# Escubo_de_LED.net
KiCad netlist of a schematic drawn in EAGLE
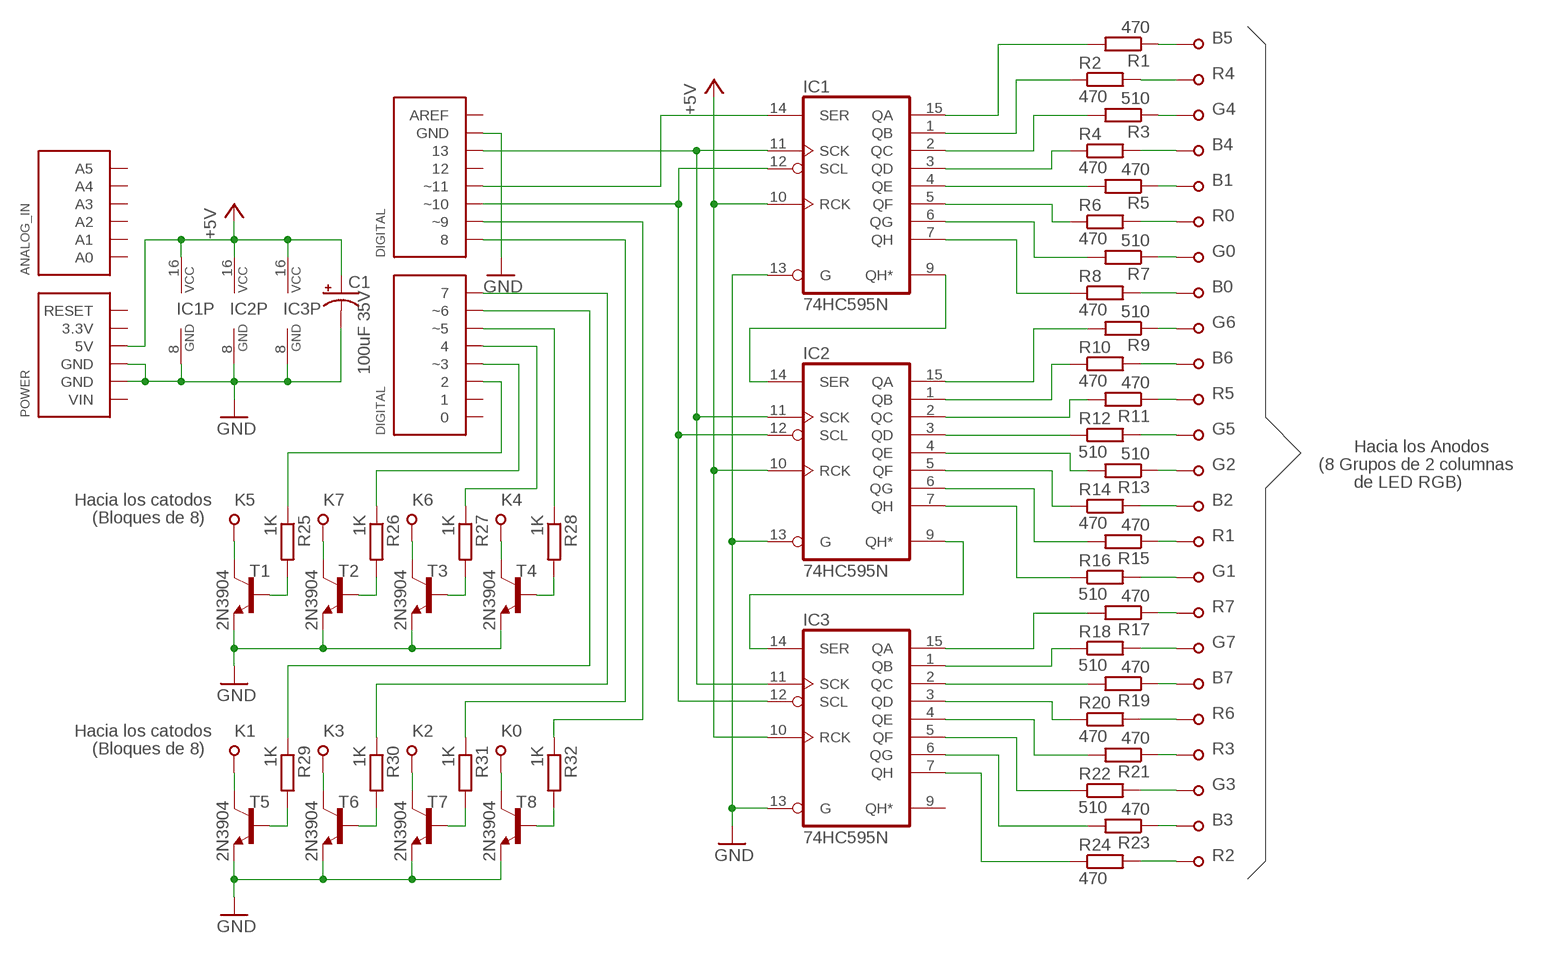
[diagram p0: schematic, sheet 1]

(export (version "E")
  (design (tool "Eeschema 10.0.6"))
  (components
    (comp (ref "C1")
      (value "100uF 35V")
      (footprint "eagle-import:E3,5-8")
      (libsource (lib "eagle-import") (part "CPOL-USE3.5-8"))
    )
    (comp (ref "IC1")
      (value "74HC595N")
      (footprint "eagle-import:DIP16")
      (libsource (lib "eagle-import") (part "74595NHC"))
    )
    (comp (ref "IC2")
      (value "74HC595N")
      (footprint "eagle-import:DIP16")
      (libsource (lib "eagle-import") (part "74595NHC"))
    )
    (comp (ref "IC3")
      (value "74HC595N")
      (footprint "eagle-import:DIP16")
      (libsource (lib "eagle-import") (part "74595NHC"))
    )
    (comp (ref "R1")
      (value "470")
      (footprint "eagle-import:0204_7")
      (libsource (lib "eagle-import") (part "R-EU_0204/7"))
    )
    (comp (ref "R2")
      (value "470")
      (footprint "eagle-import:0204_7")
      (libsource (lib "eagle-import") (part "R-EU_0204/7"))
    )
    (comp (ref "R3")
      (value "510")
      (footprint "eagle-import:0204_7")
      (libsource (lib "eagle-import") (part "R-EU_0204/7"))
    )
    (comp (ref "R4")
      (value "470")
      (footprint "eagle-import:0204_7")
      (libsource (lib "eagle-import") (part "R-EU_0204/7"))
    )
    (comp (ref "R5")
      (value "470")
      (footprint "eagle-import:0207_12")
      (libsource (lib "eagle-import") (part "R-EU_0207/12"))
    )
    (comp (ref "R6")
      (value "470")
      (footprint "eagle-import:0207_10")
      (libsource (lib "eagle-import") (part "R-EU_0207/10"))
    )
    (comp (ref "R7")
      (value "510")
      (footprint "eagle-import:0204_7")
      (libsource (lib "eagle-import") (part "R-EU_0204/7"))
    )
    (comp (ref "R8")
      (value "470")
      (footprint "eagle-import:0204_5")
      (libsource (lib "eagle-import") (part "R-EU_0204/5"))
    )
    (comp (ref "R9")
      (value "510")
      (footprint "eagle-import:0204_7")
      (libsource (lib "eagle-import") (part "R-EU_0204/7"))
    )
    (comp (ref "R10")
      (value "470")
      (footprint "eagle-import:0204_7")
      (libsource (lib "eagle-import") (part "R-EU_0204/7"))
    )
    (comp (ref "R11")
      (value "470")
      (footprint "eagle-import:0204_7")
      (libsource (lib "eagle-import") (part "R-EU_0204/7"))
    )
    (comp (ref "R12")
      (value "510")
      (footprint "eagle-import:0204_7")
      (libsource (lib "eagle-import") (part "R-EU_0204/7"))
    )
    (comp (ref "R13")
      (value "510")
      (footprint "eagle-import:0207_12")
      (libsource (lib "eagle-import") (part "R-EU_0207/12"))
    )
    (comp (ref "R14")
      (value "470")
      (footprint "eagle-import:0207_10")
      (libsource (lib "eagle-import") (part "R-EU_0207/10"))
    )
    (comp (ref "R15")
      (value "470")
      (footprint "eagle-import:0204_7")
      (libsource (lib "eagle-import") (part "R-EU_0204/7"))
    )
    (comp (ref "R16")
      (value "510")
      (footprint "eagle-import:0204_5")
      (libsource (lib "eagle-import") (part "R-EU_0204/5"))
    )
    (comp (ref "R17")
      (value "470")
      (footprint "eagle-import:0204_7")
      (libsource (lib "eagle-import") (part "R-EU_0204/7"))
    )
    (comp (ref "R18")
      (value "510")
      (footprint "eagle-import:0204_7")
      (libsource (lib "eagle-import") (part "R-EU_0204/7"))
    )
    (comp (ref "R19")
      (value "470")
      (footprint "eagle-import:0204_7")
      (libsource (lib "eagle-import") (part "R-EU_0204/7"))
    )
    (comp (ref "R20")
      (value "470")
      (footprint "eagle-import:0204_7")
      (libsource (lib "eagle-import") (part "R-EU_0204/7"))
    )
    (comp (ref "R21")
      (value "470")
      (footprint "eagle-import:0207_12")
      (libsource (lib "eagle-import") (part "R-EU_0207/12"))
    )
    (comp (ref "R22")
      (value "510")
      (footprint "eagle-import:0207_10")
      (libsource (lib "eagle-import") (part "R-EU_0207/10"))
    )
    (comp (ref "R23")
      (value "470")
      (footprint "eagle-import:0204_7")
      (libsource (lib "eagle-import") (part "R-EU_0204/7"))
    )
    (comp (ref "R24")
      (value "470")
      (footprint "eagle-import:0204_5")
      (libsource (lib "eagle-import") (part "R-EU_0204/5"))
    )
    (comp (ref "R25")
      (value "1K")
      (footprint "eagle-import:0204V")
      (libsource (lib "eagle-import") (part "R-EU_0204/2V"))
    )
    (comp (ref "R26")
      (value "1K")
      (footprint "eagle-import:0204V")
      (libsource (lib "eagle-import") (part "R-EU_0204/2V"))
    )
    (comp (ref "R27")
      (value "1K")
      (footprint "eagle-import:0204V")
      (libsource (lib "eagle-import") (part "R-EU_0204/2V"))
    )
    (comp (ref "R28")
      (value "1K")
      (footprint "eagle-import:0204V")
      (libsource (lib "eagle-import") (part "R-EU_0204/2V"))
    )
    (comp (ref "R29")
      (value "1K")
      (footprint "eagle-import:0204V")
      (libsource (lib "eagle-import") (part "R-EU_0204/2V"))
    )
    (comp (ref "R30")
      (value "1K")
      (footprint "eagle-import:0204V")
      (libsource (lib "eagle-import") (part "R-EU_0204/2V"))
    )
    (comp (ref "R31")
      (value "1K")
      (footprint "eagle-import:0204V")
      (libsource (lib "eagle-import") (part "R-EU_0204/2V"))
    )
    (comp (ref "R32")
      (value "1K")
      (footprint "eagle-import:0204V")
      (libsource (lib "eagle-import") (part "R-EU_0204/2V"))
    )
    (comp (ref "S1")
      (value "ARDUINO_SHIELD")
      (footprint "eagle-import:ARDUINO_SHIELD")
      (libsource (lib "eagle-import") (part "ARDUINO_SHIELD"))
    )
    (comp (ref "T1")
      (value "2N3904")
      (footprint "eagle-import:TO92-EBC")
      (libsource (lib "eagle-import") (part "-NPN-TO92-EBC2N3904"))
    )
    (comp (ref "T2")
      (value "2N3904")
      (footprint "eagle-import:TO92-EBC")
      (libsource (lib "eagle-import") (part "-NPN-TO92-EBC2N3904"))
    )
    (comp (ref "T3")
      (value "2N3904")
      (footprint "eagle-import:TO92-EBC")
      (libsource (lib "eagle-import") (part "-NPN-TO92-EBC2N3904"))
    )
    (comp (ref "T4")
      (value "2N3904")
      (footprint "eagle-import:TO92-EBC")
      (libsource (lib "eagle-import") (part "-NPN-TO92-EBC2N3904"))
    )
    (comp (ref "T5")
      (value "2N3904")
      (footprint "eagle-import:TO92-EBC")
      (libsource (lib "eagle-import") (part "-NPN-TO92-EBC2N3904"))
    )
    (comp (ref "T6")
      (value "2N3904")
      (footprint "eagle-import:TO92-EBC")
      (libsource (lib "eagle-import") (part "-NPN-TO92-EBC2N3904"))
    )
    (comp (ref "T7")
      (value "2N3904")
      (footprint "eagle-import:TO92-EBC")
      (libsource (lib "eagle-import") (part "-NPN-TO92-EBC2N3904"))
    )
    (comp (ref "T8")
      (value "2N3904")
      (footprint "eagle-import:TO92-EBC")
      (libsource (lib "eagle-import") (part "-NPN-TO92-EBC2N3904"))
    )
    (comp (ref "U$1")
      (value "PAD_SIMPLE_PTH")
      (footprint "eagle-import:PAD_SIMPLE_PTH")
      (libsource (lib "eagle-import") (part "PAD_SIMPLE_PTH"))
    )
    (comp (ref "U$2")
      (value "PAD_SIMPLE_PTH")
      (footprint "eagle-import:PAD_SIMPLE_PTH")
      (libsource (lib "eagle-import") (part "PAD_SIMPLE_PTH"))
    )
    (comp (ref "U$3")
      (value "PAD_SIMPLE_PTH")
      (footprint "eagle-import:PAD_SIMPLE_PTH")
      (libsource (lib "eagle-import") (part "PAD_SIMPLE_PTH"))
    )
    (comp (ref "U$4")
      (value "PAD_SIMPLE_PTH")
      (footprint "eagle-import:PAD_SIMPLE_PTH")
      (libsource (lib "eagle-import") (part "PAD_SIMPLE_PTH"))
    )
    (comp (ref "U$5")
      (value "PAD_SIMPLE_PTH")
      (footprint "eagle-import:PAD_SIMPLE_PTH")
      (libsource (lib "eagle-import") (part "PAD_SIMPLE_PTH"))
    )
    (comp (ref "U$6")
      (value "PAD_SIMPLE_PTH")
      (footprint "eagle-import:PAD_SIMPLE_PTH")
      (libsource (lib "eagle-import") (part "PAD_SIMPLE_PTH"))
    )
    (comp (ref "U$7")
      (value "PAD_SIMPLE_PTH")
      (footprint "eagle-import:PAD_SIMPLE_PTH")
      (libsource (lib "eagle-import") (part "PAD_SIMPLE_PTH"))
    )
    (comp (ref "U$8")
      (value "PAD_SIMPLE_PTH")
      (footprint "eagle-import:PAD_SIMPLE_PTH")
      (libsource (lib "eagle-import") (part "PAD_SIMPLE_PTH"))
    )
    (comp (ref "U$9")
      (value "PAD_SIMPLE_PTH")
      (footprint "eagle-import:PAD_SIMPLE_PTH")
      (libsource (lib "eagle-import") (part "PAD_SIMPLE_PTH"))
    )
    (comp (ref "U$10")
      (value "PAD_SIMPLE_PTH")
      (footprint "eagle-import:PAD_SIMPLE_PTH")
      (libsource (lib "eagle-import") (part "PAD_SIMPLE_PTH"))
    )
    (comp (ref "U$11")
      (value "PAD_SIMPLE_PTH")
      (footprint "eagle-import:PAD_SIMPLE_PTH")
      (libsource (lib "eagle-import") (part "PAD_SIMPLE_PTH"))
    )
    (comp (ref "U$12")
      (value "PAD_SIMPLE_PTH")
      (footprint "eagle-import:PAD_SIMPLE_PTH")
      (libsource (lib "eagle-import") (part "PAD_SIMPLE_PTH"))
    )
    (comp (ref "U$13")
      (value "PAD_SIMPLE_PTH")
      (footprint "eagle-import:PAD_SIMPLE_PTH")
      (libsource (lib "eagle-import") (part "PAD_SIMPLE_PTH"))
    )
    (comp (ref "U$14")
      (value "PAD_SIMPLE_PTH")
      (footprint "eagle-import:PAD_SIMPLE_PTH")
      (libsource (lib "eagle-import") (part "PAD_SIMPLE_PTH"))
    )
    (comp (ref "U$15")
      (value "PAD_SIMPLE_PTH")
      (footprint "eagle-import:PAD_SIMPLE_PTH")
      (libsource (lib "eagle-import") (part "PAD_SIMPLE_PTH"))
    )
    (comp (ref "U$16")
      (value "PAD_SIMPLE_PTH")
      (footprint "eagle-import:PAD_SIMPLE_PTH")
      (libsource (lib "eagle-import") (part "PAD_SIMPLE_PTH"))
    )
    (comp (ref "U$17")
      (value "PAD_SIMPLE_PTH")
      (footprint "eagle-import:PAD_SIMPLE_PTH")
      (libsource (lib "eagle-import") (part "PAD_SIMPLE_PTH"))
    )
    (comp (ref "U$18")
      (value "PAD_SIMPLE_PTH")
      (footprint "eagle-import:PAD_SIMPLE_PTH")
      (libsource (lib "eagle-import") (part "PAD_SIMPLE_PTH"))
    )
    (comp (ref "U$19")
      (value "PAD_SIMPLE_PTH")
      (footprint "eagle-import:PAD_SIMPLE_PTH")
      (libsource (lib "eagle-import") (part "PAD_SIMPLE_PTH"))
    )
    (comp (ref "U$20")
      (value "PAD_SIMPLE_PTH")
      (footprint "eagle-import:PAD_SIMPLE_PTH")
      (libsource (lib "eagle-import") (part "PAD_SIMPLE_PTH"))
    )
    (comp (ref "U$21")
      (value "PAD_SIMPLE_PTH")
      (footprint "eagle-import:PAD_SIMPLE_PTH")
      (libsource (lib "eagle-import") (part "PAD_SIMPLE_PTH"))
    )
    (comp (ref "U$22")
      (value "PAD_SIMPLE_PTH")
      (footprint "eagle-import:PAD_SIMPLE_PTH")
      (libsource (lib "eagle-import") (part "PAD_SIMPLE_PTH"))
    )
    (comp (ref "U$23")
      (value "PAD_SIMPLE_PTH")
      (footprint "eagle-import:PAD_SIMPLE_PTH")
      (libsource (lib "eagle-import") (part "PAD_SIMPLE_PTH"))
    )
    (comp (ref "U$24")
      (value "PAD_SIMPLE_PTH")
      (footprint "eagle-import:PAD_SIMPLE_PTH")
      (libsource (lib "eagle-import") (part "PAD_SIMPLE_PTH"))
    )
    (comp (ref "U$25")
      (value "PAD_SIMPLE_PTH")
      (footprint "eagle-import:PAD_SIMPLE_PTH")
      (libsource (lib "eagle-import") (part "PAD_SIMPLE_PTH"))
    )
    (comp (ref "U$26")
      (value "PAD_SIMPLE_PTH")
      (footprint "eagle-import:PAD_SIMPLE_PTH")
      (libsource (lib "eagle-import") (part "PAD_SIMPLE_PTH"))
    )
    (comp (ref "U$27")
      (value "PAD_SIMPLE_PTH")
      (footprint "eagle-import:PAD_SIMPLE_PTH")
      (libsource (lib "eagle-import") (part "PAD_SIMPLE_PTH"))
    )
    (comp (ref "U$28")
      (value "PAD_SIMPLE_PTH")
      (footprint "eagle-import:PAD_SIMPLE_PTH")
      (libsource (lib "eagle-import") (part "PAD_SIMPLE_PTH"))
    )
    (comp (ref "U$29")
      (value "PAD_SIMPLE_PTH")
      (footprint "eagle-import:PAD_SIMPLE_PTH")
      (libsource (lib "eagle-import") (part "PAD_SIMPLE_PTH"))
    )
    (comp (ref "U$30")
      (value "PAD_SIMPLE_PTH")
      (footprint "eagle-import:PAD_SIMPLE_PTH")
      (libsource (lib "eagle-import") (part "PAD_SIMPLE_PTH"))
    )
    (comp (ref "U$31")
      (value "PAD_SIMPLE_PTH")
      (footprint "eagle-import:PAD_SIMPLE_PTH")
      (libsource (lib "eagle-import") (part "PAD_SIMPLE_PTH"))
    )
    (comp (ref "U$32")
      (value "PAD_SIMPLE_PTH")
      (footprint "eagle-import:PAD_SIMPLE_PTH")
      (libsource (lib "eagle-import") (part "PAD_SIMPLE_PTH"))
    )
  )
  (nets
    (net (code "1") (name "+5V") (class "Default")
      (node (ref "C1") (pin "+") (pinfunction "+_+") (pintype "passive"))
      (node (ref "IC1") (pin "10") (pinfunction "RCK_10") (pintype "input"))
      (node (ref "IC1") (pin "16") (pinfunction "VCC_16") (pintype "power_in"))
      (node (ref "IC2") (pin "10") (pinfunction "RCK_10") (pintype "input"))
      (node (ref "IC2") (pin "16") (pinfunction "VCC_16") (pintype "power_in"))
      (node (ref "IC3") (pin "10") (pinfunction "RCK_10") (pintype "input"))
      (node (ref "IC3") (pin "16") (pinfunction "VCC_16") (pintype "power_in"))
      (node (ref "S1") (pin "5V") (pinfunction "5V_5V") (pintype "bidirectional"))
    )
    (net (code "2") (name "GND") (class "Default")
      (node (ref "C1") (pin "-") (pinfunction "-_-") (pintype "passive"))
      (node (ref "IC1") (pin "13") (pinfunction "G_13") (pintype "input"))
      (node (ref "IC1") (pin "8") (pinfunction "GND_8") (pintype "power_in"))
      (node (ref "IC2") (pin "13") (pinfunction "G_13") (pintype "input"))
      (node (ref "IC2") (pin "8") (pinfunction "GND_8") (pintype "power_in"))
      (node (ref "IC3") (pin "13") (pinfunction "G_13") (pintype "input"))
      (node (ref "IC3") (pin "8") (pinfunction "GND_8") (pintype "power_in"))
      (node (ref "S1") (pin "GND") (pinfunction "GND_GND") (pintype "bidirectional"))
      (node (ref "S1") (pin "GND@1") (pinfunction "GND_GND@1") (pintype "bidirectional"))
      (node (ref "S1") (pin "GND@2") (pinfunction "GND_GND@2") (pintype "bidirectional"))
      (node (ref "T1") (pin "E") (pinfunction "E_E") (pintype "passive"))
      (node (ref "T2") (pin "E") (pinfunction "E_E") (pintype "passive"))
      (node (ref "T3") (pin "E") (pinfunction "E_E") (pintype "passive"))
      (node (ref "T4") (pin "E") (pinfunction "E_E") (pintype "passive"))
      (node (ref "T5") (pin "E") (pinfunction "E_E") (pintype "passive"))
      (node (ref "T6") (pin "E") (pinfunction "E_E") (pintype "passive"))
      (node (ref "T7") (pin "E") (pinfunction "E_E") (pintype "passive"))
      (node (ref "T8") (pin "E") (pinfunction "E_E") (pintype "passive"))
    )
    (net (code "3") (name "Net-(IC1A-QA)") (class "Default")
      (node (ref "IC1") (pin "15") (pinfunction "QA_15") (pintype "tri_state"))
      (node (ref "R1") (pin "2") (pinfunction "2_2") (pintype "passive"))
    )
    (net (code "4") (name "Net-(IC1A-QB)") (class "Default")
      (node (ref "IC1") (pin "1") (pinfunction "QB_1") (pintype "tri_state"))
      (node (ref "R2") (pin "1") (pinfunction "1_1") (pintype "passive"))
    )
    (net (code "5") (name "Net-(IC1A-QC)") (class "Default")
      (node (ref "IC1") (pin "2") (pinfunction "QC_2") (pintype "tri_state"))
      (node (ref "R3") (pin "2") (pinfunction "2_2") (pintype "passive"))
    )
    (net (code "6") (name "Net-(IC1A-QD)") (class "Default")
      (node (ref "IC1") (pin "3") (pinfunction "QD_3") (pintype "tri_state"))
      (node (ref "R4") (pin "1") (pinfunction "1_1") (pintype "passive"))
    )
    (net (code "7") (name "Net-(IC1A-QE)") (class "Default")
      (node (ref "IC1") (pin "4") (pinfunction "QE_4") (pintype "tri_state"))
      (node (ref "R5") (pin "2") (pinfunction "2_2") (pintype "passive"))
    )
    (net (code "8") (name "Net-(IC1A-QF)") (class "Default")
      (node (ref "IC1") (pin "5") (pinfunction "QF_5") (pintype "tri_state"))
      (node (ref "R6") (pin "1") (pinfunction "1_1") (pintype "passive"))
    )
    (net (code "9") (name "Net-(IC1A-QG)") (class "Default")
      (node (ref "IC1") (pin "6") (pinfunction "QG_6") (pintype "tri_state"))
      (node (ref "R7") (pin "2") (pinfunction "2_2") (pintype "passive"))
    )
    (net (code "10") (name "Net-(IC1A-QH)") (class "Default")
      (node (ref "IC1") (pin "7") (pinfunction "QH_7") (pintype "tri_state"))
      (node (ref "R8") (pin "1") (pinfunction "1_1") (pintype "passive"))
    )
    (net (code "11") (name "Net-(IC1A-QH*)") (class "Default")
      (node (ref "IC1") (pin "9") (pinfunction "QH*_9") (pintype "tri_state"))
      (node (ref "IC2") (pin "14") (pinfunction "SER_14") (pintype "input"))
    )
    (net (code "12") (name "Net-(IC1A-SCK)") (class "Default")
      (node (ref "IC1") (pin "11") (pinfunction "SCK_11") (pintype "input"))
      (node (ref "IC2") (pin "11") (pinfunction "SCK_11") (pintype "input"))
      (node (ref "IC3") (pin "11") (pinfunction "SCK_11") (pintype "input"))
      (node (ref "S1") (pin "13") (pinfunction "13_13") (pintype "bidirectional"))
    )
    (net (code "13") (name "Net-(IC1A-SCL)") (class "Default")
      (node (ref "IC1") (pin "12") (pinfunction "SCL_12") (pintype "input"))
      (node (ref "IC2") (pin "12") (pinfunction "SCL_12") (pintype "input"))
      (node (ref "IC3") (pin "12") (pinfunction "SCL_12") (pintype "input"))
      (node (ref "S1") (pin "~10") (pinfunction "~{10}_~10") (pintype "bidirectional"))
    )
    (net (code "14") (name "Net-(IC1A-SER)") (class "Default")
      (node (ref "IC1") (pin "14") (pinfunction "SER_14") (pintype "input"))
      (node (ref "S1") (pin "~11") (pinfunction "~{11}_~11") (pintype "bidirectional"))
    )
    (net (code "15") (name "Net-(IC2A-QA)") (class "Default")
      (node (ref "IC2") (pin "15") (pinfunction "QA_15") (pintype "tri_state"))
      (node (ref "R9") (pin "2") (pinfunction "2_2") (pintype "passive"))
    )
    (net (code "16") (name "Net-(IC2A-QB)") (class "Default")
      (node (ref "IC2") (pin "1") (pinfunction "QB_1") (pintype "tri_state"))
      (node (ref "R10") (pin "1") (pinfunction "1_1") (pintype "passive"))
    )
    (net (code "17") (name "Net-(IC2A-QC)") (class "Default")
      (node (ref "IC2") (pin "2") (pinfunction "QC_2") (pintype "tri_state"))
      (node (ref "R11") (pin "2") (pinfunction "2_2") (pintype "passive"))
    )
    (net (code "18") (name "Net-(IC2A-QD)") (class "Default")
      (node (ref "IC2") (pin "3") (pinfunction "QD_3") (pintype "tri_state"))
      (node (ref "R12") (pin "1") (pinfunction "1_1") (pintype "passive"))
    )
    (net (code "19") (name "Net-(IC2A-QE)") (class "Default")
      (node (ref "IC2") (pin "4") (pinfunction "QE_4") (pintype "tri_state"))
      (node (ref "R13") (pin "2") (pinfunction "2_2") (pintype "passive"))
    )
    (net (code "20") (name "Net-(IC2A-QF)") (class "Default")
      (node (ref "IC2") (pin "5") (pinfunction "QF_5") (pintype "tri_state"))
      (node (ref "R14") (pin "1") (pinfunction "1_1") (pintype "passive"))
    )
    (net (code "21") (name "Net-(IC2A-QG)") (class "Default")
      (node (ref "IC2") (pin "6") (pinfunction "QG_6") (pintype "tri_state"))
      (node (ref "R15") (pin "2") (pinfunction "2_2") (pintype "passive"))
    )
    (net (code "22") (name "Net-(IC2A-QH)") (class "Default")
      (node (ref "IC2") (pin "7") (pinfunction "QH_7") (pintype "tri_state"))
      (node (ref "R16") (pin "1") (pinfunction "1_1") (pintype "passive"))
    )
    (net (code "23") (name "Net-(IC2A-QH*)") (class "Default")
      (node (ref "IC2") (pin "9") (pinfunction "QH*_9") (pintype "tri_state"))
      (node (ref "IC3") (pin "14") (pinfunction "SER_14") (pintype "input"))
    )
    (net (code "24") (name "Net-(IC3A-QA)") (class "Default")
      (node (ref "IC3") (pin "15") (pinfunction "QA_15") (pintype "tri_state"))
      (node (ref "R17") (pin "2") (pinfunction "2_2") (pintype "passive"))
    )
    (net (code "25") (name "Net-(IC3A-QB)") (class "Default")
      (node (ref "IC3") (pin "1") (pinfunction "QB_1") (pintype "tri_state"))
      (node (ref "R18") (pin "1") (pinfunction "1_1") (pintype "passive"))
    )
    (net (code "26") (name "Net-(IC3A-QC)") (class "Default")
      (node (ref "IC3") (pin "2") (pinfunction "QC_2") (pintype "tri_state"))
      (node (ref "R19") (pin "2") (pinfunction "2_2") (pintype "passive"))
    )
    (net (code "27") (name "Net-(IC3A-QD)") (class "Default")
      (node (ref "IC3") (pin "3") (pinfunction "QD_3") (pintype "tri_state"))
      (node (ref "R20") (pin "1") (pinfunction "1_1") (pintype "passive"))
    )
    (net (code "28") (name "Net-(IC3A-QE)") (class "Default")
      (node (ref "IC3") (pin "4") (pinfunction "QE_4") (pintype "tri_state"))
      (node (ref "R21") (pin "2") (pinfunction "2_2") (pintype "passive"))
    )
    (net (code "29") (name "Net-(IC3A-QF)") (class "Default")
      (node (ref "IC3") (pin "5") (pinfunction "QF_5") (pintype "tri_state"))
      (node (ref "R22") (pin "1") (pinfunction "1_1") (pintype "passive"))
    )
    (net (code "30") (name "Net-(IC3A-QG)") (class "Default")
      (node (ref "IC3") (pin "6") (pinfunction "QG_6") (pintype "tri_state"))
      (node (ref "R23") (pin "2") (pinfunction "2_2") (pintype "passive"))
    )
    (net (code "31") (name "Net-(IC3A-QH)") (class "Default")
      (node (ref "IC3") (pin "7") (pinfunction "QH_7") (pintype "tri_state"))
      (node (ref "R24") (pin "1") (pinfunction "1_1") (pintype "passive"))
    )
    (net (code "32") (name "Net-(R1-Pad1)") (class "Default")
      (node (ref "R1") (pin "1") (pinfunction "1_1") (pintype "passive"))
      (node (ref "U$1") (pin "P$1") (pinfunction "P$1_P$1") (pintype "bidirectional"))
    )
    (net (code "33") (name "Net-(R2-Pad2)") (class "Default")
      (node (ref "R2") (pin "2") (pinfunction "2_2") (pintype "passive"))
      (node (ref "U$2") (pin "P$1") (pinfunction "P$1_P$1") (pintype "bidirectional"))
    )
    (net (code "34") (name "Net-(R3-Pad1)") (class "Default")
      (node (ref "R3") (pin "1") (pinfunction "1_1") (pintype "passive"))
      (node (ref "U$3") (pin "P$1") (pinfunction "P$1_P$1") (pintype "bidirectional"))
    )
    (net (code "35") (name "Net-(R4-Pad2)") (class "Default")
      (node (ref "R4") (pin "2") (pinfunction "2_2") (pintype "passive"))
      (node (ref "U$4") (pin "P$1") (pinfunction "P$1_P$1") (pintype "bidirectional"))
    )
    (net (code "36") (name "Net-(R5-Pad1)") (class "Default")
      (node (ref "R5") (pin "1") (pinfunction "1_1") (pintype "passive"))
      (node (ref "U$5") (pin "P$1") (pinfunction "P$1_P$1") (pintype "bidirectional"))
    )
    (net (code "37") (name "Net-(R6-Pad2)") (class "Default")
      (node (ref "R6") (pin "2") (pinfunction "2_2") (pintype "passive"))
      (node (ref "U$6") (pin "P$1") (pinfunction "P$1_P$1") (pintype "bidirectional"))
    )
    (net (code "38") (name "Net-(R7-Pad1)") (class "Default")
      (node (ref "R7") (pin "1") (pinfunction "1_1") (pintype "passive"))
      (node (ref "U$7") (pin "P$1") (pinfunction "P$1_P$1") (pintype "bidirectional"))
    )
    (net (code "39") (name "Net-(R8-Pad2)") (class "Default")
      (node (ref "R8") (pin "2") (pinfunction "2_2") (pintype "passive"))
      (node (ref "U$8") (pin "P$1") (pinfunction "P$1_P$1") (pintype "bidirectional"))
    )
    (net (code "40") (name "Net-(R9-Pad1)") (class "Default")
      (node (ref "R9") (pin "1") (pinfunction "1_1") (pintype "passive"))
      (node (ref "U$9") (pin "P$1") (pinfunction "P$1_P$1") (pintype "bidirectional"))
    )
    (net (code "41") (name "Net-(R10-Pad2)") (class "Default")
      (node (ref "R10") (pin "2") (pinfunction "2_2") (pintype "passive"))
      (node (ref "U$10") (pin "P$1") (pinfunction "P$1_P$1") (pintype "bidirectional"))
    )
    (net (code "42") (name "Net-(R11-Pad1)") (class "Default")
      (node (ref "R11") (pin "1") (pinfunction "1_1") (pintype "passive"))
      (node (ref "U$11") (pin "P$1") (pinfunction "P$1_P$1") (pintype "bidirectional"))
    )
    (net (code "43") (name "Net-(R12-Pad2)") (class "Default")
      (node (ref "R12") (pin "2") (pinfunction "2_2") (pintype "passive"))
      (node (ref "U$12") (pin "P$1") (pinfunction "P$1_P$1") (pintype "bidirectional"))
    )
    (net (code "44") (name "Net-(R13-Pad1)") (class "Default")
      (node (ref "R13") (pin "1") (pinfunction "1_1") (pintype "passive"))
      (node (ref "U$13") (pin "P$1") (pinfunction "P$1_P$1") (pintype "bidirectional"))
    )
    (net (code "45") (name "Net-(R14-Pad2)") (class "Default")
      (node (ref "R14") (pin "2") (pinfunction "2_2") (pintype "passive"))
      (node (ref "U$14") (pin "P$1") (pinfunction "P$1_P$1") (pintype "bidirectional"))
    )
    (net (code "46") (name "Net-(R15-Pad1)") (class "Default")
      (node (ref "R15") (pin "1") (pinfunction "1_1") (pintype "passive"))
      (node (ref "U$15") (pin "P$1") (pinfunction "P$1_P$1") (pintype "bidirectional"))
    )
    (net (code "47") (name "Net-(R16-Pad2)") (class "Default")
      (node (ref "R16") (pin "2") (pinfunction "2_2") (pintype "passive"))
      (node (ref "U$16") (pin "P$1") (pinfunction "P$1_P$1") (pintype "bidirectional"))
    )
    (net (code "48") (name "Net-(R17-Pad1)") (class "Default")
      (node (ref "R17") (pin "1") (pinfunction "1_1") (pintype "passive"))
      (node (ref "U$17") (pin "P$1") (pinfunction "P$1_P$1") (pintype "bidirectional"))
    )
    (net (code "49") (name "Net-(R18-Pad2)") (class "Default")
      (node (ref "R18") (pin "2") (pinfunction "2_2") (pintype "passive"))
      (node (ref "U$18") (pin "P$1") (pinfunction "P$1_P$1") (pintype "bidirectional"))
    )
    (net (code "50") (name "Net-(R19-Pad1)") (class "Default")
      (node (ref "R19") (pin "1") (pinfunction "1_1") (pintype "passive"))
      (node (ref "U$19") (pin "P$1") (pinfunction "P$1_P$1") (pintype "bidirectional"))
    )
    (net (code "51") (name "Net-(R20-Pad2)") (class "Default")
      (node (ref "R20") (pin "2") (pinfunction "2_2") (pintype "passive"))
      (node (ref "U$20") (pin "P$1") (pinfunction "P$1_P$1") (pintype "bidirectional"))
    )
    (net (code "52") (name "Net-(R21-Pad1)") (class "Default")
      (node (ref "R21") (pin "1") (pinfunction "1_1") (pintype "passive"))
      (node (ref "U$21") (pin "P$1") (pinfunction "P$1_P$1") (pintype "bidirectional"))
    )
    (net (code "53") (name "Net-(R22-Pad2)") (class "Default")
      (node (ref "R22") (pin "2") (pinfunction "2_2") (pintype "passive"))
      (node (ref "U$22") (pin "P$1") (pinfunction "P$1_P$1") (pintype "bidirectional"))
    )
    (net (code "54") (name "Net-(R23-Pad1)") (class "Default")
      (node (ref "R23") (pin "1") (pinfunction "1_1") (pintype "passive"))
      (node (ref "U$23") (pin "P$1") (pinfunction "P$1_P$1") (pintype "bidirectional"))
    )
    (net (code "55") (name "Net-(R24-Pad2)") (class "Default")
      (node (ref "R24") (pin "2") (pinfunction "2_2") (pintype "passive"))
      (node (ref "U$24") (pin "P$1") (pinfunction "P$1_P$1") (pintype "bidirectional"))
    )
    (net (code "56") (name "Net-(R25-Pad1)") (class "Default")
      (node (ref "R25") (pin "1") (pinfunction "1_1") (pintype "passive"))
      (node (ref "S1") (pin "2") (pinfunction "2_2") (pintype "bidirectional"))
    )
    (net (code "57") (name "Net-(R25-Pad2)") (class "Default")
      (node (ref "R25") (pin "2") (pinfunction "2_2") (pintype "passive"))
      (node (ref "T1") (pin "B") (pinfunction "B_B") (pintype "passive"))
    )
    (net (code "58") (name "Net-(R26-Pad2)") (class "Default")
      (node (ref "R26") (pin "2") (pinfunction "2_2") (pintype "passive"))
      (node (ref "T2") (pin "B") (pinfunction "B_B") (pintype "passive"))
    )
    (net (code "59") (name "Net-(R27-Pad1)") (class "Default")
      (node (ref "R27") (pin "1") (pinfunction "1_1") (pintype "passive"))
      (node (ref "S1") (pin "4") (pinfunction "4_4") (pintype "bidirectional"))
    )
    (net (code "60") (name "Net-(R27-Pad2)") (class "Default")
      (node (ref "R27") (pin "2") (pinfunction "2_2") (pintype "passive"))
      (node (ref "T3") (pin "B") (pinfunction "B_B") (pintype "passive"))
    )
    (net (code "61") (name "Net-(R28-Pad2)") (class "Default")
      (node (ref "R28") (pin "2") (pinfunction "2_2") (pintype "passive"))
      (node (ref "T4") (pin "B") (pinfunction "B_B") (pintype "passive"))
    )
    (net (code "62") (name "Net-(R29-Pad2)") (class "Default")
      (node (ref "R29") (pin "2") (pinfunction "2_2") (pintype "passive"))
      (node (ref "T5") (pin "B") (pinfunction "B_B") (pintype "passive"))
    )
    (net (code "63") (name "Net-(R30-Pad1)") (class "Default")
      (node (ref "R30") (pin "1") (pinfunction "1_1") (pintype "passive"))
      (node (ref "S1") (pin "7") (pinfunction "7_7") (pintype "bidirectional"))
    )
    (net (code "64") (name "Net-(R30-Pad2)") (class "Default")
      (node (ref "R30") (pin "2") (pinfunction "2_2") (pintype "passive"))
      (node (ref "T6") (pin "B") (pinfunction "B_B") (pintype "passive"))
    )
    (net (code "65") (name "Net-(R31-Pad1)") (class "Default")
      (node (ref "R31") (pin "1") (pinfunction "1_1") (pintype "passive"))
      (node (ref "S1") (pin "8") (pinfunction "8_8") (pintype "bidirectional"))
    )
    (net (code "66") (name "Net-(R31-Pad2)") (class "Default")
      (node (ref "R31") (pin "2") (pinfunction "2_2") (pintype "passive"))
      (node (ref "T7") (pin "B") (pinfunction "B_B") (pintype "passive"))
    )
    (net (code "67") (name "Net-(R32-Pad2)") (class "Default")
      (node (ref "R32") (pin "2") (pinfunction "2_2") (pintype "passive"))
      (node (ref "T8") (pin "B") (pinfunction "B_B") (pintype "passive"))
    )
    (net (code "68") (name "Net-(S1B-~{9})") (class "Default")
      (node (ref "R32") (pin "1") (pinfunction "1_1") (pintype "passive"))
      (node (ref "S1") (pin "~9") (pinfunction "~{9}_~9") (pintype "bidirectional"))
    )
    (net (code "69") (name "Net-(S1C-~{3})") (class "Default")
      (node (ref "R26") (pin "1") (pinfunction "1_1") (pintype "passive"))
      (node (ref "S1") (pin "~3") (pinfunction "~{3}_~3") (pintype "bidirectional"))
    )
    (net (code "70") (name "Net-(S1C-~{5})") (class "Default")
      (node (ref "R28") (pin "1") (pinfunction "1_1") (pintype "passive"))
      (node (ref "S1") (pin "~5") (pinfunction "~{5}_~5") (pintype "bidirectional"))
    )
    (net (code "71") (name "Net-(S1C-~{6})") (class "Default")
      (node (ref "R29") (pin "1") (pinfunction "1_1") (pintype "passive"))
      (node (ref "S1") (pin "~6") (pinfunction "~{6}_~6") (pintype "bidirectional"))
    )
    (net (code "72") (name "Net-(T1-PadC)") (class "Default")
      (node (ref "T1") (pin "C") (pinfunction "C_C") (pintype "passive"))
      (node (ref "U$25") (pin "P$1") (pinfunction "P$1_P$1") (pintype "bidirectional"))
    )
    (net (code "73") (name "Net-(T2-PadC)") (class "Default")
      (node (ref "T2") (pin "C") (pinfunction "C_C") (pintype "passive"))
      (node (ref "U$26") (pin "P$1") (pinfunction "P$1_P$1") (pintype "bidirectional"))
    )
    (net (code "74") (name "Net-(T3-PadC)") (class "Default")
      (node (ref "T3") (pin "C") (pinfunction "C_C") (pintype "passive"))
      (node (ref "U$27") (pin "P$1") (pinfunction "P$1_P$1") (pintype "bidirectional"))
    )
    (net (code "75") (name "Net-(T4-PadC)") (class "Default")
      (node (ref "T4") (pin "C") (pinfunction "C_C") (pintype "passive"))
      (node (ref "U$28") (pin "P$1") (pinfunction "P$1_P$1") (pintype "bidirectional"))
    )
    (net (code "76") (name "Net-(T5-PadC)") (class "Default")
      (node (ref "T5") (pin "C") (pinfunction "C_C") (pintype "passive"))
      (node (ref "U$29") (pin "P$1") (pinfunction "P$1_P$1") (pintype "bidirectional"))
    )
    (net (code "77") (name "Net-(T6-PadC)") (class "Default")
      (node (ref "T6") (pin "C") (pinfunction "C_C") (pintype "passive"))
      (node (ref "U$30") (pin "P$1") (pinfunction "P$1_P$1") (pintype "bidirectional"))
    )
    (net (code "78") (name "Net-(T7-PadC)") (class "Default")
      (node (ref "T7") (pin "C") (pinfunction "C_C") (pintype "passive"))
      (node (ref "U$31") (pin "P$1") (pinfunction "P$1_P$1") (pintype "bidirectional"))
    )
    (net (code "79") (name "Net-(T8-PadC)") (class "Default")
      (node (ref "T8") (pin "C") (pinfunction "C_C") (pintype "passive"))
      (node (ref "U$32") (pin "P$1") (pinfunction "P$1_P$1") (pintype "bidirectional"))
    )
    (net (code "80") (name "unconnected-(IC3A-QH*-Pad9)") (class "Default")
      (node (ref "IC3") (pin "9") (pinfunction "QH*_9") (pintype "tri_state"))
    )
    (net (code "81") (name "unconnected-(S1-Pad0)") (class "Default")
      (node (ref "S1") (pin "0") (pinfunction "0_0") (pintype "bidirectional"))
    )
    (net (code "82") (name "unconnected-(S1-Pad1)") (class "Default")
      (node (ref "S1") (pin "1") (pinfunction "1_1") (pintype "bidirectional"))
    )
    (net (code "83") (name "unconnected-(S1-Pad3.3V)") (class "Default")
      (node (ref "S1") (pin "3.3V") (pinfunction "3.3V_3.3V") (pintype "bidirectional"))
    )
    (net (code "84") (name "unconnected-(S1-Pad12)") (class "Default")
      (node (ref "S1") (pin "12") (pinfunction "12_12") (pintype "bidirectional"))
    )
    (net (code "85") (name "unconnected-(S1-PadA0)") (class "Default")
      (node (ref "S1") (pin "A0") (pinfunction "A0_A0") (pintype "bidirectional"))
    )
    (net (code "86") (name "unconnected-(S1-PadA1)") (class "Default")
      (node (ref "S1") (pin "A1") (pinfunction "A1_A1") (pintype "bidirectional"))
    )
    (net (code "87") (name "unconnected-(S1-PadA2)") (class "Default")
      (node (ref "S1") (pin "A2") (pinfunction "A2_A2") (pintype "bidirectional"))
    )
    (net (code "88") (name "unconnected-(S1-PadA3)") (class "Default")
      (node (ref "S1") (pin "A3") (pinfunction "A3_A3") (pintype "bidirectional"))
    )
    (net (code "89") (name "unconnected-(S1-PadA4)") (class "Default")
      (node (ref "S1") (pin "A4") (pinfunction "A4_A4") (pintype "bidirectional"))
    )
    (net (code "90") (name "unconnected-(S1-PadA5)") (class "Default")
      (node (ref "S1") (pin "A5") (pinfunction "A5_A5") (pintype "bidirectional"))
    )
    (net (code "91") (name "unconnected-(S1-PadAREF)") (class "Default")
      (node (ref "S1") (pin "AREF") (pinfunction "AREF_AREF") (pintype "bidirectional"))
    )
    (net (code "92") (name "unconnected-(S1-PadRESET)") (class "Default")
      (node (ref "S1") (pin "RESET") (pinfunction "RESET_RESET") (pintype "bidirectional"))
    )
    (net (code "93") (name "unconnected-(S1-PadVIN)") (class "Default")
      (node (ref "S1") (pin "VIN") (pinfunction "VIN_VIN") (pintype "bidirectional"))
    )
  )
)
